# M5_Access_Switch_Output.net
KiCad netlist of a schematic drawn in EAGLE
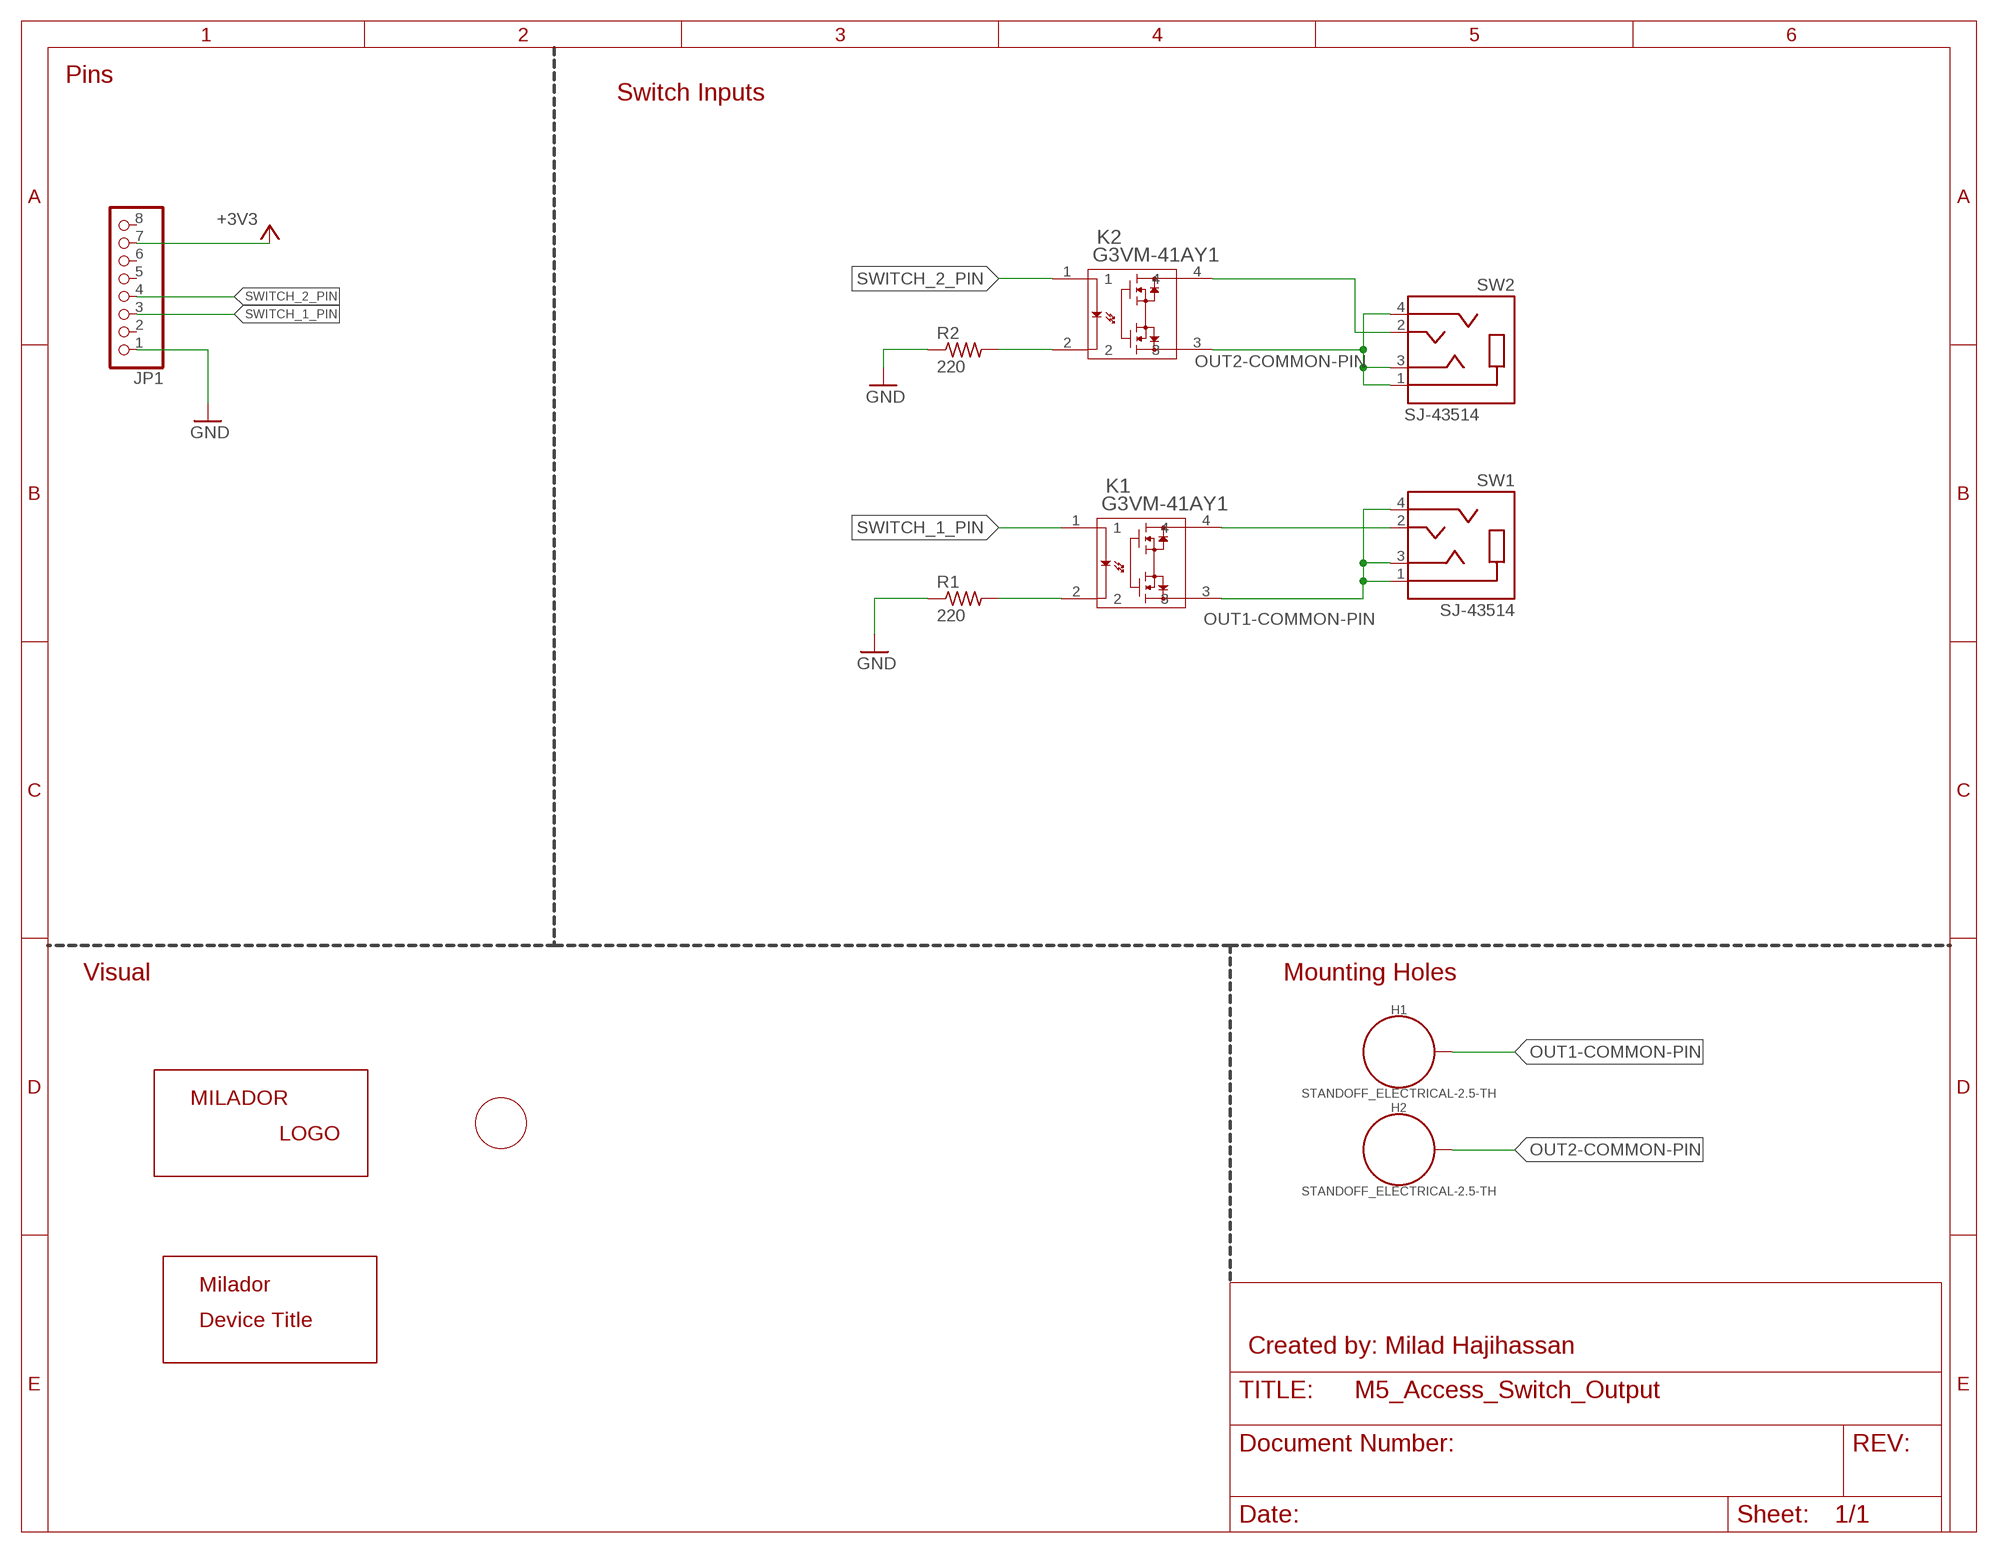
[diagram p0: schematic, sheet 1]

(export (version "E")
  (design (tool "Eeschema 10.0.6"))
  (components
    (comp (ref "H1")
      (value "STANDOFF_ELECTRICAL-2.5-TH")
      (footprint "eagle-import:STANDOFF-ELECTRICAL-2.5-TH")
      (libsource (lib "eagle-import") (part "STANDOFF_ELECTRICAL-2.5-TH"))
    )
    (comp (ref "H2")
      (value "STANDOFF_ELECTRICAL-2.5-TH")
      (footprint "eagle-import:STANDOFF-ELECTRICAL-2.5-TH")
      (libsource (lib "eagle-import") (part "STANDOFF_ELECTRICAL-2.5-TH"))
    )
    (comp (ref "JP1")
      (value "HEADER_MALE-1X8ROUND-RA")
      (footprint "eagle-import:1X08_ROUND_RA")
      (libsource (lib "eagle-import") (part "HEADER_MALE-1X8ROUND-RA"))
    )
    (comp (ref "K1")
      (value "G3VM-41AY1")
      (footprint "eagle-import:A-DIP4_THD_OMR")
      (fields (field (name "COPYRIGHT") "Copyright (C) 2022 Ultra Librarian. All rights reserved."))
      (libsource (lib "eagle-import") (part "G3VM-41AY1"))
    )
    (comp (ref "K2")
      (value "G3VM-41AY1")
      (footprint "eagle-import:A-DIP4_THD_OMR")
      (fields (field (name "COPYRIGHT") "Copyright (C) 2022 Ultra Librarian. All rights reserved."))
      (libsource (lib "eagle-import") (part "G3VM-41AY1"))
    )
    (comp (ref "LABEL_DEVICE_TOP")
      (value "MILADOR-DEVICE-M5-ACCESS-SWITCH")
      (footprint "eagle-import:MILADOR_M5_ACCESS_SWITCH")
      (libsource (lib "eagle-import") (part "MILADOR-DEVICE-M5-ACCESS-SWITCH"))
    )
    (comp (ref "LABEL_LOGO_TOP")
      (value "MILADOR-LOGO-SM")
      (footprint "eagle-import:MILADOR_LOGO2")
      (libsource (lib "eagle-import") (part "MILADOR-LOGO-SM"))
    )
    (comp (ref "LABEL_OUTPUT_TOP")
      (value "MILADOR-SWITCH-NAME-SW-OUTPUT")
      (footprint "eagle-import:SWITCH-OUTPUT")
      (libsource (lib "eagle-import") (part "MILADOR-SWITCH-NAME-SW-OUTPUT"))
    )
    (comp (ref "R1")
      (value "220")
      (footprint "eagle-import:RESISTOR_0204_5")
      (libsource (lib "eagle-import") (part "RESISTOR-US-0204/5"))
    )
    (comp (ref "R2")
      (value "220")
      (footprint "eagle-import:RESISTOR_0204_5")
      (libsource (lib "eagle-import") (part "RESISTOR-US-0204/5"))
    )
    (comp (ref "SW1")
      (value "SJ-43514")
      (footprint "eagle-import:CUI_SJ-43514")
      (libsource (lib "eagle-import") (part "SJ-43514"))
    )
    (comp (ref "SW2")
      (value "SJ-43514")
      (footprint "eagle-import:CUI_SJ-43514")
      (libsource (lib "eagle-import") (part "SJ-43514"))
    )
  )
  (nets
    (net (code "1") (name "+3V3") (class "Default")
      (node (ref "JP1") (pin "7") (pinfunction "7_7") (pintype "passive"))
    )
    (net (code "2") (name "GND") (class "Default")
      (node (ref "JP1") (pin "1") (pinfunction "1_1") (pintype "passive"))
      (node (ref "R1") (pin "1") (pinfunction "1_1") (pintype "passive"))
      (node (ref "R2") (pin "1") (pinfunction "1_1") (pintype "passive"))
    )
    (net (code "3") (name "Net-(K1-Pad2)") (class "Default")
      (node (ref "K1") (pin "2") (pinfunction "2_2") (pintype "passive"))
      (node (ref "R1") (pin "2") (pinfunction "2_2") (pintype "passive"))
    )
    (net (code "4") (name "Net-(K2-Pad2)") (class "Default")
      (node (ref "K2") (pin "2") (pinfunction "2_2") (pintype "passive"))
      (node (ref "R2") (pin "2") (pinfunction "2_2") (pintype "passive"))
    )
    (net (code "5") (name "Net-(SW1-TIP)") (class "Default")
      (node (ref "K1") (pin "4") (pinfunction "4_4") (pintype "passive"))
      (node (ref "SW1") (pin "2") (pinfunction "TIP_2") (pintype "passive"))
    )
    (net (code "6") (name "Net-(SW2-TIP)") (class "Default")
      (node (ref "K2") (pin "4") (pinfunction "4_4") (pintype "passive"))
      (node (ref "SW2") (pin "2") (pinfunction "TIP_2") (pintype "passive"))
    )
    (net (code "7") (name "OUT1-COMMON-PIN") (class "Default")
      (node (ref "H1") (pin "P1") (pinfunction "P$1_P1") (pintype "bidirectional"))
      (node (ref "K1") (pin "3") (pinfunction "3_3") (pintype "passive"))
      (node (ref "SW1") (pin "1") (pinfunction "SLEEVE_1") (pintype "passive"))
      (node (ref "SW1") (pin "3") (pinfunction "RING1_3") (pintype "passive"))
      (node (ref "SW1") (pin "4") (pinfunction "RING2_4") (pintype "passive"))
    )
    (net (code "8") (name "OUT2-COMMON-PIN") (class "Default")
      (node (ref "H2") (pin "P1") (pinfunction "P$1_P1") (pintype "bidirectional"))
      (node (ref "K2") (pin "3") (pinfunction "3_3") (pintype "passive"))
      (node (ref "SW2") (pin "1") (pinfunction "SLEEVE_1") (pintype "passive"))
      (node (ref "SW2") (pin "3") (pinfunction "RING1_3") (pintype "passive"))
      (node (ref "SW2") (pin "4") (pinfunction "RING2_4") (pintype "passive"))
    )
    (net (code "9") (name "SWITCH_1_PIN") (class "Default")
      (node (ref "JP1") (pin "3") (pinfunction "3_3") (pintype "passive"))
      (node (ref "K1") (pin "1") (pinfunction "1_1") (pintype "passive"))
    )
    (net (code "10") (name "SWITCH_2_PIN") (class "Default")
      (node (ref "JP1") (pin "4") (pinfunction "4_4") (pintype "passive"))
      (node (ref "K2") (pin "1") (pinfunction "1_1") (pintype "passive"))
    )
    (net (code "11") (name "unconnected-(JP1-Pad2)") (class "Default")
      (node (ref "JP1") (pin "2") (pinfunction "2_2") (pintype "passive"))
    )
    (net (code "12") (name "unconnected-(JP1-Pad5)") (class "Default")
      (node (ref "JP1") (pin "5") (pinfunction "5_5") (pintype "passive"))
    )
    (net (code "13") (name "unconnected-(JP1-Pad6)") (class "Default")
      (node (ref "JP1") (pin "6") (pinfunction "6_6") (pintype "passive"))
    )
    (net (code "14") (name "unconnected-(JP1-Pad8)") (class "Default")
      (node (ref "JP1") (pin "8") (pinfunction "8_8") (pintype "passive"))
    )
  )
)
